# NP-100v12.net
KiCad netlist of a schematic drawn in EAGLE
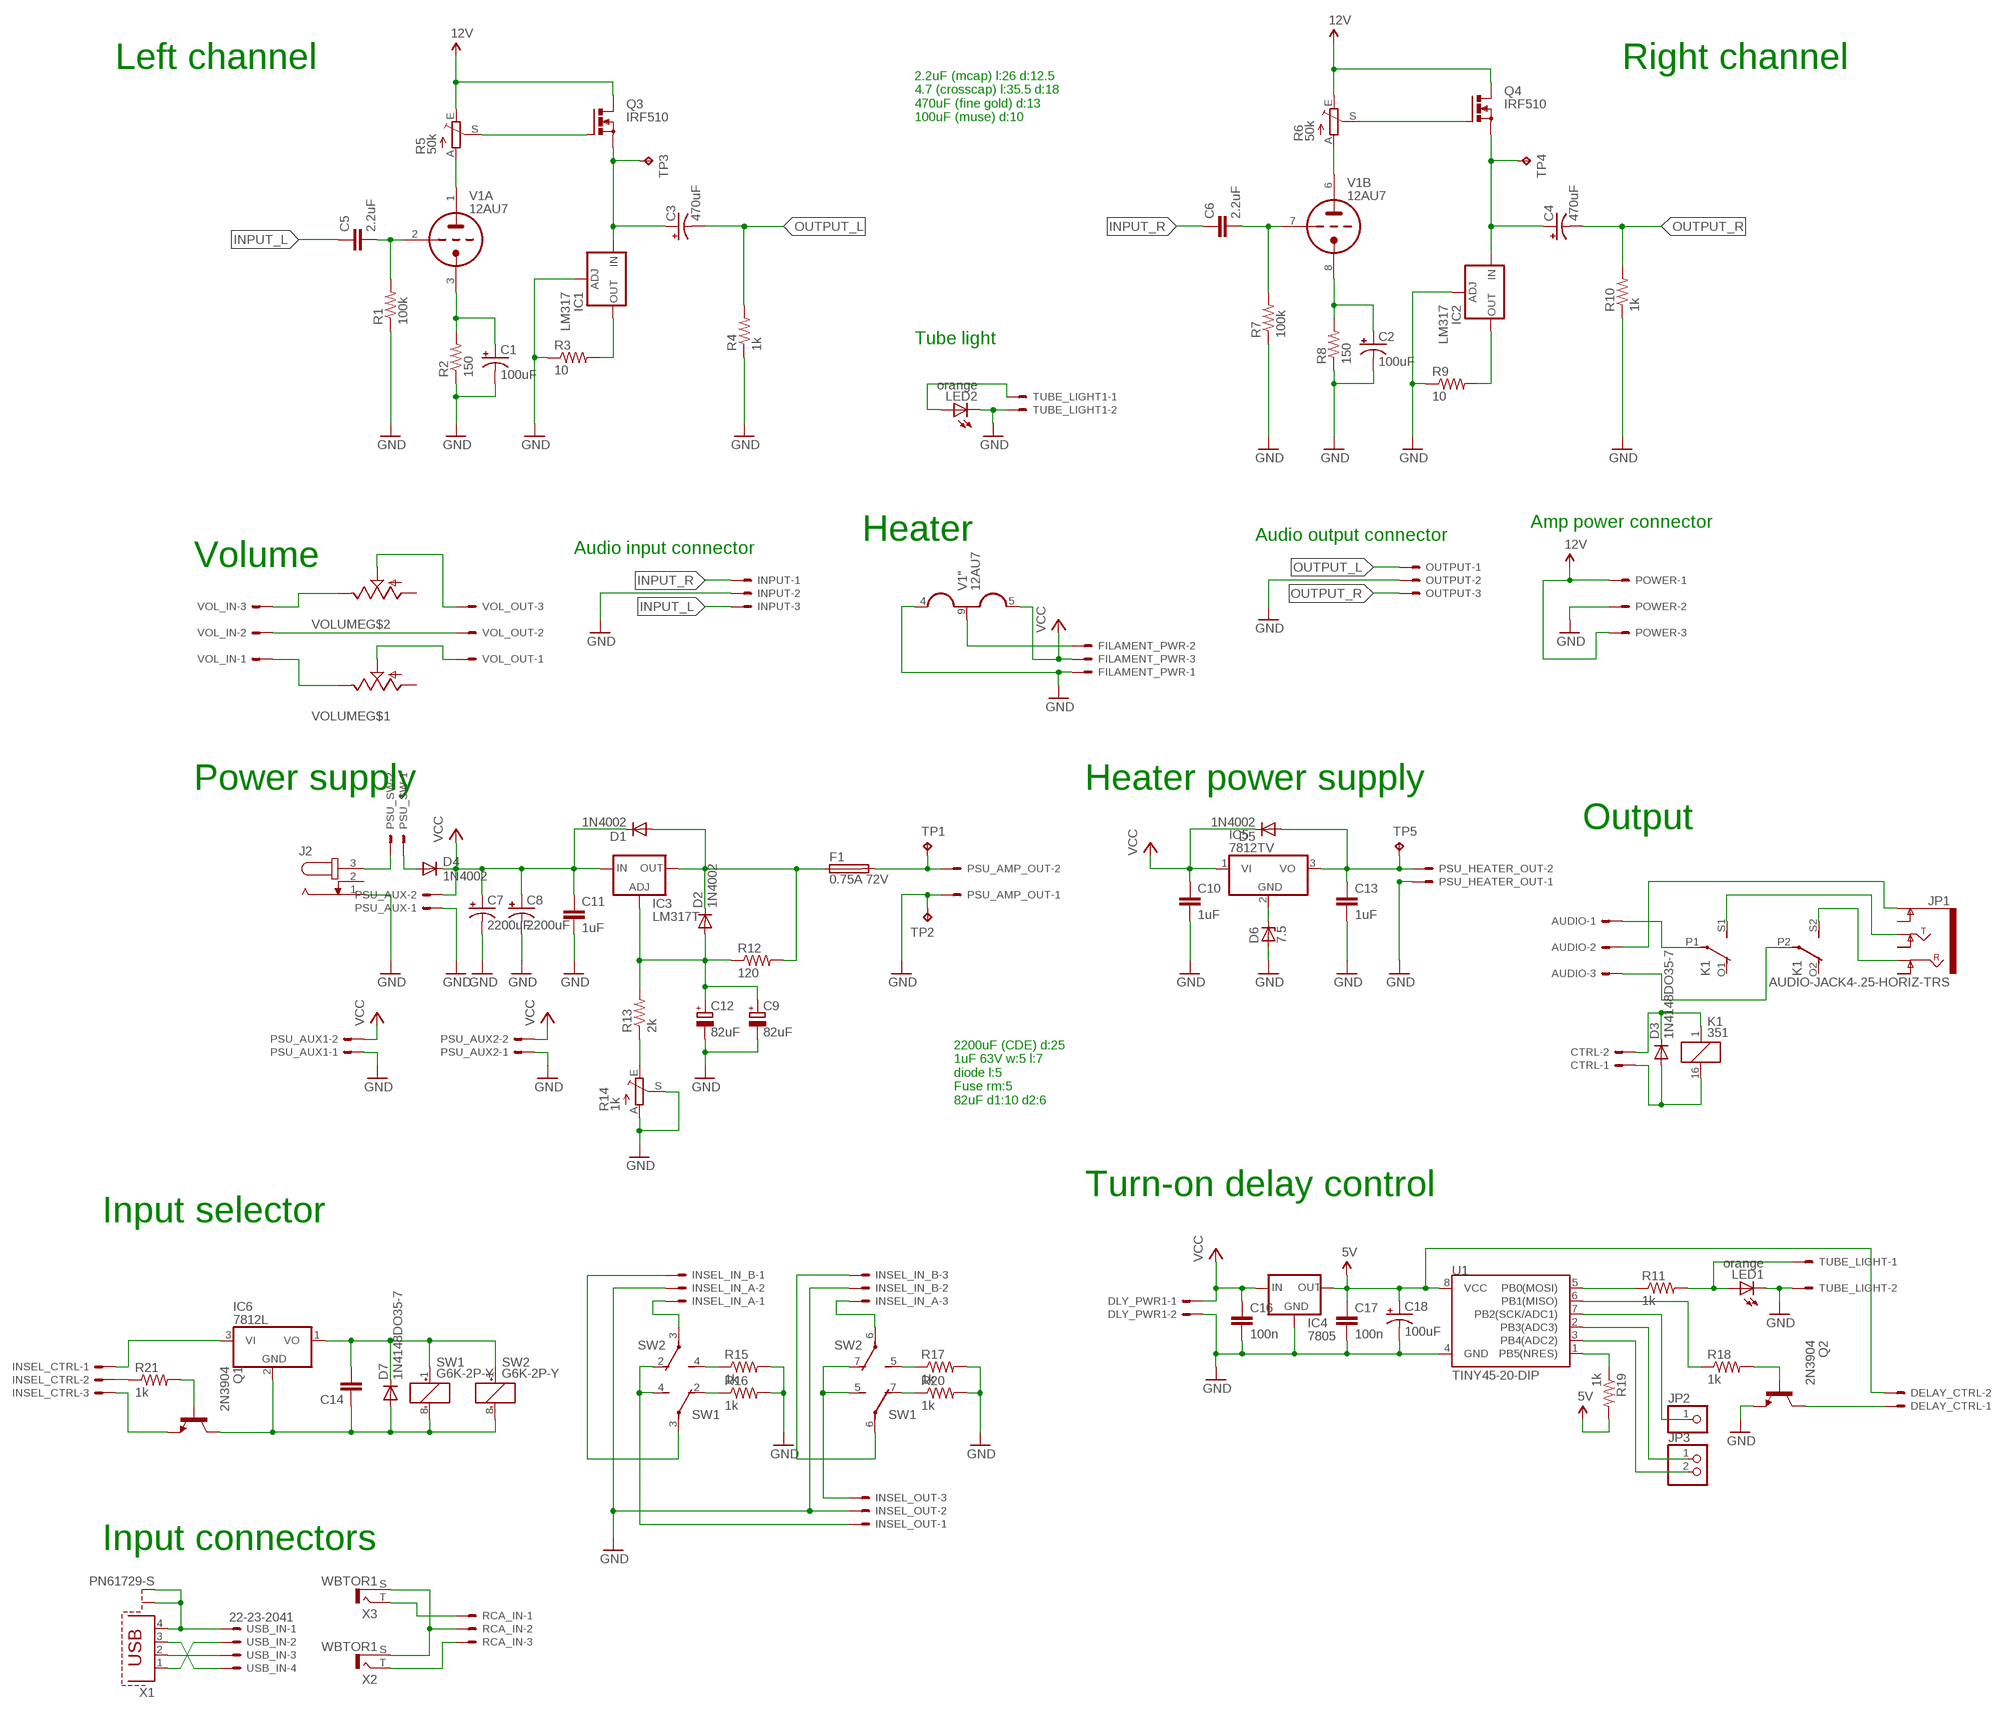
[diagram p0: schematic, sheet 1]

(export (version "E")
  (design (tool "Eeschema 10.0.6"))
  (components
    (comp (ref "AUDIO")
      (value "22-23-2031")
      (footprint "eagle-import:22-23-2031")
      (fields (field (name "MF") "MOLEX"))
      (libsource (lib "eagle-import") (part "22-23-2031"))
    )
    (comp (ref "C1")
      (value "100uF")
      (footprint "eagle-import:E5-10,5")
      (libsource (lib "eagle-import") (part "CPOL-USE5-10.5"))
    )
    (comp (ref "C2")
      (value "100uF")
      (footprint "eagle-import:E5-10,5")
      (libsource (lib "eagle-import") (part "CPOL-USE5-10.5"))
    )
    (comp (ref "C3")
      (value "470uF")
      (footprint "eagle-import:E5-13")
      (libsource (lib "eagle-import") (part "CPOL-USE5-13"))
    )
    (comp (ref "C4")
      (value "470uF")
      (footprint "eagle-import:E5-13")
      (libsource (lib "eagle-import") (part "CPOL-USE5-13"))
    )
    (comp (ref "C5")
      (value "2.2uF")
      (footprint "eagle-import:C37.5B19")
      (libsource (lib "eagle-import") (part "C37/19"))
    )
    (comp (ref "C6")
      (value "2.2uF")
      (footprint "eagle-import:C37.5B19")
      (libsource (lib "eagle-import") (part "C37/19"))
    )
    (comp (ref "C7")
      (value "2200uF")
      (footprint "eagle-import:EB25D")
      (libsource (lib "eagle-import") (part "CPOL-USE10-25"))
    )
    (comp (ref "C8")
      (value "2200uF")
      (footprint "eagle-import:EB25D")
      (libsource (lib "eagle-import") (part "CPOL-USE10-25"))
    )
    (comp (ref "C9")
      (value "82uF")
      (footprint "eagle-import:E2,5-6")
      (libsource (lib "eagle-import") (part "CPOL-EUE2.5-6"))
    )
    (comp (ref "C10")
      (value "1uF")
      (footprint "eagle-import:C5B4.5")
      (libsource (lib "eagle-import") (part "C5/4.5"))
    )
    (comp (ref "C11")
      (value "1uF")
      (footprint "eagle-import:C5B4.5")
      (libsource (lib "eagle-import") (part "C5/4.5"))
    )
    (comp (ref "C12")
      (value "82uF")
      (footprint "eagle-import:E5-10,5")
      (libsource (lib "eagle-import") (part "CPOL-EUE5-10.5"))
    )
    (comp (ref "C13")
      (value "1uF")
      (footprint "eagle-import:C5B4.5")
      (libsource (lib "eagle-import") (part "C5/4.5"))
    )
    (comp (ref "C14")
      (value "C5/2.5")
      (footprint "eagle-import:C5B2.5")
      (libsource (lib "eagle-import") (part "C5/2.5"))
    )
    (comp (ref "C16")
      (value "100n")
      (footprint "eagle-import:CAP-PTH-5MM")
      (libsource (lib "eagle-import") (part "CAPPTH1"))
    )
    (comp (ref "C17")
      (value "100n")
      (footprint "eagle-import:CAP-PTH-5MM")
      (libsource (lib "eagle-import") (part "CAPPTH1"))
    )
    (comp (ref "C18")
      (value "100uF")
      (footprint "eagle-import:E2,5-7")
      (libsource (lib "eagle-import") (part "CPOL-USE2.5-7"))
    )
    (comp (ref "CTRL")
      (value "22-23-2021")
      (footprint "eagle-import:22-23-2021")
      (fields (field (name "MF") "MOLEX"))
      (libsource (lib "eagle-import") (part "22-23-2021"))
    )
    (comp (ref "D1")
      (value "1N4002")
      (footprint "eagle-import:D-7.5")
      (libsource (lib "eagle-import") (part "DIODE-D-7.5"))
    )
    (comp (ref "D2")
      (value "1N4002")
      (footprint "eagle-import:D-7.5")
      (libsource (lib "eagle-import") (part "DIODE-D-7.5"))
    )
    (comp (ref "D3")
      (value "1N4148DO35-7")
      (footprint "eagle-import:DO35-7")
      (libsource (lib "eagle-import") (part "1N4148DO35-7"))
    )
    (comp (ref "D4")
      (value "1N4002")
      (footprint "eagle-import:D-5")
      (libsource (lib "eagle-import") (part "DIODE-D-5"))
    )
    (comp (ref "D5")
      (value "1N4002")
      (footprint "eagle-import:D-7.5")
      (libsource (lib "eagle-import") (part "DIODE-D-7.5"))
    )
    (comp (ref "D6")
      (value "7.5")
      (footprint "eagle-import:DO34Z7")
      (libsource (lib "eagle-import") (part "ZENER-DIODEDO34-7"))
    )
    (comp (ref "D7")
      (value "1N4148DO35-7")
      (footprint "eagle-import:DO35-7")
      (libsource (lib "eagle-import") (part "1N4148DO35-7"))
    )
    (comp (ref "DELAY_CTRL")
      (value "22-23-2021")
      (footprint "eagle-import:22-23-2021")
      (fields (field (name "MF") "MOLEX"))
      (libsource (lib "eagle-import") (part "22-23-2021"))
    )
    (comp (ref "DLY_PWR1")
      (value "22-23-2021")
      (footprint "eagle-import:22-23-2021")
      (fields (field (name "MF") "MOLEX"))
      (libsource (lib "eagle-import") (part "22-23-2021"))
    )
    (comp (ref "F1")
      (value "0.75A 72V")
      (footprint "eagle-import:TE5")
      (libsource (lib "eagle-import") (part "TE5"))
    )
    (comp (ref "FILAMENT_PWR")
      (value "22-23-2031")
      (footprint "eagle-import:22-23-2031")
      (fields (field (name "MF") "MOLEX"))
      (libsource (lib "eagle-import") (part "22-23-2031"))
    )
    (comp (ref "IC1")
      (value "LM317")
      (footprint "eagle-import:317TS")
      (libsource (lib "eagle-import") (part "LM317TS"))
    )
    (comp (ref "IC2")
      (value "LM317")
      (footprint "eagle-import:317TS")
      (libsource (lib "eagle-import") (part "LM317TS"))
    )
    (comp (ref "IC3")
      (value "LM317T")
      (footprint "eagle-import:317TS")
      (libsource (lib "eagle-import") (part "LM317TS"))
    )
    (comp (ref "IC4")
      (value "7805")
      (footprint "eagle-import:TO-92")
      (libsource (lib "eagle-import") (part "V_REG_78XXTO-92_UNTESTED"))
    )
    (comp (ref "IC5")
      (value "7812TV")
      (footprint "eagle-import:TO220V")
      (libsource (lib "eagle-import") (part "78TV12"))
    )
    (comp (ref "IC6")
      (value "7812L")
      (footprint "eagle-import:TO92")
      (libsource (lib "eagle-import") (part "78L12"))
    )
    (comp (ref "INPUT")
      (value "22-23-2031")
      (footprint "eagle-import:22-23-2031")
      (fields (field (name "MF") "MOLEX"))
      (libsource (lib "eagle-import") (part "22-23-2031"))
    )
    (comp (ref "INSEL_CTRL")
      (value "22-23-2031")
      (footprint "eagle-import:22-23-2031")
      (fields (field (name "MF") "MOLEX"))
      (libsource (lib "eagle-import") (part "22-23-2031"))
    )
    (comp (ref "INSEL_IN_A")
      (value "22-23-2031")
      (footprint "eagle-import:22-23-2031")
      (fields (field (name "MF") "MOLEX"))
      (libsource (lib "eagle-import") (part "22-23-2031"))
    )
    (comp (ref "INSEL_IN_B")
      (value "22-23-2031")
      (footprint "eagle-import:22-23-2031")
      (fields (field (name "MF") "MOLEX"))
      (libsource (lib "eagle-import") (part "22-23-2031"))
    )
    (comp (ref "INSEL_OUT")
      (value "22-23-2031")
      (footprint "eagle-import:22-23-2031")
      (fields (field (name "MF") "MOLEX"))
      (libsource (lib "eagle-import") (part "22-23-2031"))
    )
    (comp (ref "J2")
      (value "JACK-PLUG0")
      (footprint "eagle-import:SPC4077")
      (libsource (lib "eagle-import") (part "JACK-PLUG0"))
    )
    (comp (ref "JP1")
      (value "AUDIO-JACK4-.25-HORIZ-TRS")
      (footprint "eagle-import:AUDIO-JACK-.25-INCH-HORIZ-PTH")
      (libsource (lib "eagle-import") (part "AUDIO-JACK4-.25-HORIZ-TRS"))
    )
    (comp (ref "JP2")
      (value "PINHD-1X1")
      (footprint "eagle-import:1X01")
      (libsource (lib "eagle-import") (part "PINHD-1X1"))
    )
    (comp (ref "JP3")
      (value "PINHD-1X2")
      (footprint "eagle-import:1X02")
      (libsource (lib "eagle-import") (part "PINHD-1X2"))
    )
    (comp (ref "K1")
      (value "351")
      (footprint "eagle-import:351")
      (libsource (lib "eagle-import") (part "351"))
    )
    (comp (ref "LED1")
      (value "orange")
      (footprint "eagle-import:LED3MM")
      (libsource (lib "eagle-import") (part "LED3MM"))
    )
    (comp (ref "LED2")
      (value "orange")
      (footprint "eagle-import:LED3MM")
      (libsource (lib "eagle-import") (part "LED3MM"))
    )
    (comp (ref "OUTPUT")
      (value "22-23-2031")
      (footprint "eagle-import:22-23-2031")
      (fields (field (name "MF") "MOLEX"))
      (libsource (lib "eagle-import") (part "22-23-2031"))
    )
    (comp (ref "POWER")
      (value "22-23-2031")
      (footprint "eagle-import:22-23-2031")
      (fields (field (name "MF") "MOLEX"))
      (libsource (lib "eagle-import") (part "22-23-2031"))
    )
    (comp (ref "PSU_AMP_OUT")
      (value "22-23-2021")
      (footprint "eagle-import:22-23-2021")
      (fields (field (name "MF") "MOLEX"))
      (libsource (lib "eagle-import") (part "22-23-2021"))
    )
    (comp (ref "PSU_AUX")
      (value "22-23-2021")
      (footprint "eagle-import:22-23-2021")
      (fields (field (name "MF") "MOLEX"))
      (libsource (lib "eagle-import") (part "22-23-2021"))
    )
    (comp (ref "PSU_AUX1")
      (value "22-23-2021")
      (footprint "eagle-import:22-23-2021")
      (fields (field (name "MF") "MOLEX"))
      (libsource (lib "eagle-import") (part "22-23-2021"))
    )
    (comp (ref "PSU_AUX2")
      (value "22-23-2021")
      (footprint "eagle-import:22-23-2021")
      (fields (field (name "MF") "MOLEX"))
      (libsource (lib "eagle-import") (part "22-23-2021"))
    )
    (comp (ref "PSU_HEATER_OUT")
      (value "22-23-2021")
      (footprint "eagle-import:22-23-2021")
      (fields (field (name "MF") "MOLEX"))
      (libsource (lib "eagle-import") (part "22-23-2021"))
    )
    (comp (ref "PSU_SW")
      (value "22-23-2021")
      (footprint "eagle-import:22-23-2021")
      (fields (field (name "MF") "MOLEX"))
      (libsource (lib "eagle-import") (part "22-23-2021"))
    )
    (comp (ref "Q1")
      (value "2N3904")
      (footprint "eagle-import:TO92")
      (libsource (lib "eagle-import") (part "2N3904"))
    )
    (comp (ref "Q2")
      (value "2N3904")
      (footprint "eagle-import:TO92")
      (libsource (lib "eagle-import") (part "2N3904"))
    )
    (comp (ref "Q3")
      (value "IRF510")
      (footprint "eagle-import:TO220BV")
      (libsource (lib "eagle-import") (part "PMOSFET_NTO220BV"))
    )
    (comp (ref "Q4")
      (value "IRF510")
      (footprint "eagle-import:TO220BV")
      (libsource (lib "eagle-import") (part "PMOSFET_NTO220BV"))
    )
    (comp (ref "R1")
      (value "100k")
      (footprint "eagle-import:0207_10")
      (libsource (lib "eagle-import") (part "R-US_0207/10"))
    )
    (comp (ref "R2")
      (value "150")
      (footprint "eagle-import:0207_10")
      (libsource (lib "eagle-import") (part "R-US_0207/10"))
    )
    (comp (ref "R3")
      (value "10")
      (footprint "eagle-import:0207_10")
      (libsource (lib "eagle-import") (part "R-US_0207/10"))
    )
    (comp (ref "R4")
      (value "1k")
      (footprint "eagle-import:0207_10")
      (libsource (lib "eagle-import") (part "R-US_0207/10"))
    )
    (comp (ref "R5")
      (value "50k")
      (footprint "eagle-import:SP19L")
      (libsource (lib "eagle-import") (part "TRIM_EU-B90P"))
    )
    (comp (ref "R6")
      (value "50k")
      (footprint "eagle-import:SP19L")
      (libsource (lib "eagle-import") (part "TRIM_EU-B90P"))
    )
    (comp (ref "R7")
      (value "100k")
      (footprint "eagle-import:0207_10")
      (libsource (lib "eagle-import") (part "R-US_0207/10"))
    )
    (comp (ref "R8")
      (value "150")
      (footprint "eagle-import:0207_10")
      (libsource (lib "eagle-import") (part "R-US_0207/10"))
    )
    (comp (ref "R9")
      (value "10")
      (footprint "eagle-import:0207_10")
      (libsource (lib "eagle-import") (part "R-US_0207/10"))
    )
    (comp (ref "R10")
      (value "1k")
      (footprint "eagle-import:0207_10")
      (libsource (lib "eagle-import") (part "R-US_0207/10"))
    )
    (comp (ref "R11")
      (value "1k")
      (footprint "eagle-import:0204_7")
      (libsource (lib "eagle-import") (part "R-US_0204/7"))
    )
    (comp (ref "R12")
      (value "120")
      (footprint "eagle-import:AXIAL-0.3")
      (libsource (lib "eagle-import") (part "RESISTORAXIAL-0.3"))
    )
    (comp (ref "R13")
      (value "2k")
      (footprint "eagle-import:AXIAL-0.3")
      (libsource (lib "eagle-import") (part "RESISTORAXIAL-0.3"))
    )
    (comp (ref "R14")
      (value "1k")
      (footprint "eagle-import:S64Y")
      (libsource (lib "eagle-import") (part "TRIM_EU-S64Y"))
    )
    (comp (ref "R15")
      (value "1k")
      (footprint "eagle-import:AXIAL-0.3")
      (libsource (lib "eagle-import") (part "RESISTORAXIAL-0.3"))
    )
    (comp (ref "R16")
      (value "1k")
      (footprint "eagle-import:AXIAL-0.3")
      (libsource (lib "eagle-import") (part "RESISTORAXIAL-0.3"))
    )
    (comp (ref "R17")
      (value "1k")
      (footprint "eagle-import:AXIAL-0.3")
      (libsource (lib "eagle-import") (part "RESISTORAXIAL-0.3"))
    )
    (comp (ref "R18")
      (value "1k")
      (footprint "eagle-import:0204_7")
      (libsource (lib "eagle-import") (part "R-US_0204/7"))
    )
    (comp (ref "R19")
      (value "1k")
      (footprint "eagle-import:0204_7")
      (libsource (lib "eagle-import") (part "R-US_0204/7"))
    )
    (comp (ref "R20")
      (value "1k")
      (footprint "eagle-import:AXIAL-0.3")
      (libsource (lib "eagle-import") (part "RESISTORAXIAL-0.3"))
    )
    (comp (ref "R21")
      (value "1k")
      (footprint "eagle-import:0204_7")
      (libsource (lib "eagle-import") (part "R-US_0204/7"))
    )
    (comp (ref "RCA_IN")
      (value "22-23-2031")
      (footprint "eagle-import:22-23-2031")
      (fields (field (name "MF") "MOLEX"))
      (libsource (lib "eagle-import") (part "22-23-2031"))
    )
    (comp (ref "SW1")
      (value "G6K-2P-Y")
      (footprint "eagle-import:G6K-2P-Y")
      (fields (field (name "MF") "OMRON COMPONENTS USA") (field (name "MPN") "G6K-2P-Y DC12"))
      (libsource (lib "eagle-import") (part "G6K-2P-Y"))
    )
    (comp (ref "SW2")
      (value "G6K-2P-Y")
      (footprint "eagle-import:G6K-2P-Y")
      (fields (field (name "MF") "OMRON COMPONENTS USA") (field (name "MPN") "G6K-2P-Y DC12"))
      (libsource (lib "eagle-import") (part "G6K-2P-Y"))
    )
    (comp (ref "TP1")
      (value "TPPAD1-17")
      (footprint "eagle-import:P1-17")
      (libsource (lib "eagle-import") (part "TPPAD1-17"))
    )
    (comp (ref "TP2")
      (value "TPPAD1-17")
      (footprint "eagle-import:P1-17")
      (libsource (lib "eagle-import") (part "TPPAD1-17"))
    )
    (comp (ref "TP3")
      (value "TPPAD1-17")
      (footprint "eagle-import:P1-17")
      (libsource (lib "eagle-import") (part "TPPAD1-17"))
    )
    (comp (ref "TP4")
      (value "TPPAD1-17")
      (footprint "eagle-import:P1-17")
      (libsource (lib "eagle-import") (part "TPPAD1-17"))
    )
    (comp (ref "TP5")
      (value "TPPAD1-17")
      (footprint "eagle-import:P1-17")
      (libsource (lib "eagle-import") (part "TPPAD1-17"))
    )
    (comp (ref "TUBE_LIGHT")
      (value "22-23-2021")
      (footprint "eagle-import:22-23-2021")
      (fields (field (name "MF") "MOLEX"))
      (libsource (lib "eagle-import") (part "22-23-2021"))
    )
    (comp (ref "TUBE_LIGHT1")
      (value "22-23-2021")
      (footprint "eagle-import:22-23-2021")
      (fields (field (name "MF") "MOLEX"))
      (libsource (lib "eagle-import") (part "22-23-2021"))
    )
    (comp (ref "U1")
      (value "TINY45-20-DIP")
      (footprint "eagle-import:DIP08")
      (libsource (lib "eagle-import") (part "ATTINY45TINY45-20-DIP"))
    )
    (comp (ref "USB_IN")
      (value "22-23-2041")
      (footprint "eagle-import:22-23-2041")
      (fields (field (name "MF") "MOLEX"))
      (libsource (lib "eagle-import") (part "22-23-2041"))
    )
    (comp (ref "V1")
      (value "12AU7")
      (footprint "eagle-import:NOVAL")
      (libsource (lib "eagle-import") (part "12AU7-P"))
    )
    (comp (ref "VOLUME")
      (value "ALPS_BLUE")
      (footprint "eagle-import:ALPS_RK27")
      (libsource (lib "eagle-import") (part "ALPS_BLUE"))
    )
    (comp (ref "VOL_IN")
      (value "22-23-2031")
      (footprint "eagle-import:22-23-2031")
      (fields (field (name "MF") "MOLEX"))
      (libsource (lib "eagle-import") (part "22-23-2031"))
    )
    (comp (ref "VOL_OUT")
      (value "22-23-2031")
      (footprint "eagle-import:22-23-2031")
      (fields (field (name "MF") "MOLEX"))
      (libsource (lib "eagle-import") (part "22-23-2031"))
    )
    (comp (ref "X1")
      (value "PN61729-S")
      (footprint "eagle-import:PN61729-S")
      (libsource (lib "eagle-import") (part "PN61729-S"))
    )
    (comp (ref "X2")
      (value "WBTOR1")
      (footprint "eagle-import:WBTOR1")
      (fields (field (name "MPN") "WBTOR 1 BLACK"))
      (libsource (lib "eagle-import") (part "WBTOR1"))
    )
    (comp (ref "X3")
      (value "WBTOR1")
      (footprint "eagle-import:WBTOR1")
      (fields (field (name "MPN") "WBTOR 1 BLACK"))
      (libsource (lib "eagle-import") (part "WBTOR1"))
    )
  )
  (nets
    (net (code "1") (name "5V") (class "Default")
      (node (ref "C17") (pin "1") (pinfunction "1_1") (pintype "passive"))
      (node (ref "C18") (pin "+") (pinfunction "+_+") (pintype "passive"))
      (node (ref "DELAY_CTRL") (pin "2") (pinfunction "S_2") (pintype "passive"))
      (node (ref "IC4") (pin "3") (pinfunction "OUT_3") (pintype "output"))
      (node (ref "R19") (pin "2") (pinfunction "2_2") (pintype "passive"))
      (node (ref "U1") (pin "8") (pinfunction "VCC_8") (pintype "bidirectional"))
    )
    (net (code "2") (name "12V") (class "Default")
      (node (ref "POWER") (pin "1") (pinfunction "S_1") (pintype "passive"))
      (node (ref "POWER") (pin "3") (pinfunction "S_3") (pintype "passive"))
      (node (ref "Q3") (pin "D") (pinfunction "D_D") (pintype "passive"))
      (node (ref "Q4") (pin "D") (pinfunction "D_D") (pintype "passive"))
      (node (ref "R5") (pin "E") (pinfunction "E_E") (pintype "passive"))
      (node (ref "R6") (pin "E") (pinfunction "E_E") (pintype "passive"))
    )
    (net (code "3") (name "GND") (class "Default")
      (node (ref "C1") (pin "-") (pinfunction "-_-") (pintype "passive"))
      (node (ref "C10") (pin "2") (pinfunction "2_2") (pintype "passive"))
      (node (ref "C11") (pin "2") (pinfunction "2_2") (pintype "passive"))
      (node (ref "C12") (pin "-") (pinfunction "-_-") (pintype "passive"))
      (node (ref "C13") (pin "2") (pinfunction "2_2") (pintype "passive"))
      (node (ref "C16") (pin "2") (pinfunction "2_2") (pintype "passive"))
      (node (ref "C17") (pin "2") (pinfunction "2_2") (pintype "passive"))
      (node (ref "C18") (pin "-") (pinfunction "-_-") (pintype "passive"))
      (node (ref "C2") (pin "-") (pinfunction "-_-") (pintype "passive"))
      (node (ref "C7") (pin "-") (pinfunction "-_-") (pintype "passive"))
      (node (ref "C8") (pin "-") (pinfunction "-_-") (pintype "passive"))
      (node (ref "C9") (pin "-") (pinfunction "-_-") (pintype "passive"))
      (node (ref "D6") (pin "A") (pinfunction "A_A") (pintype "passive"))
      (node (ref "DLY_PWR1") (pin "2") (pinfunction "S_2") (pintype "passive"))
      (node (ref "FILAMENT_PWR") (pin "1") (pinfunction "S_1") (pintype "passive"))
      (node (ref "IC1") (pin "1") (pinfunction "ADJ_1") (pintype "input"))
      (node (ref "IC2") (pin "1") (pinfunction "ADJ_1") (pintype "input"))
      (node (ref "IC4") (pin "1") (pinfunction "GND_1") (pintype "input"))
      (node (ref "INPUT") (pin "2") (pinfunction "S_2") (pintype "passive"))
      (node (ref "INSEL_IN_A") (pin "2") (pinfunction "S_2") (pintype "passive"))
      (node (ref "INSEL_IN_B") (pin "2") (pinfunction "S_2") (pintype "passive"))
      (node (ref "INSEL_OUT") (pin "2") (pinfunction "S_2") (pintype "passive"))
      (node (ref "J2") (pin "1") (pinfunction "1_1") (pintype "passive"))
      (node (ref "LED1") (pin "K") (pinfunction "C_K") (pintype "passive"))
      (node (ref "LED2") (pin "K") (pinfunction "C_K") (pintype "passive"))
      (node (ref "OUTPUT") (pin "2") (pinfunction "S_2") (pintype "passive"))
      (node (ref "POWER") (pin "2") (pinfunction "S_2") (pintype "passive"))
      (node (ref "PSU_AMP_OUT") (pin "1") (pinfunction "S_1") (pintype "passive"))
      (node (ref "PSU_AUX") (pin "1") (pinfunction "S_1") (pintype "passive"))
      (node (ref "PSU_AUX1") (pin "1") (pinfunction "S_1") (pintype "passive"))
      (node (ref "PSU_AUX2") (pin "1") (pinfunction "S_1") (pintype "passive"))
      (node (ref "PSU_HEATER_OUT") (pin "1") (pinfunction "S_1") (pintype "passive"))
      (node (ref "Q2") (pin "3") (pinfunction "E_3") (pintype "passive"))
      (node (ref "R1") (pin "1") (pinfunction "1_1") (pintype "passive"))
      (node (ref "R10") (pin "1") (pinfunction "1_1") (pintype "passive"))
      (node (ref "R14") (pin "A") (pinfunction "A_A") (pintype "passive"))
      (node (ref "R14") (pin "S") (pinfunction "S_S") (pintype "passive"))
      (node (ref "R15") (pin "P$2") (pinfunction "2_P$2") (pintype "passive"))
      (node (ref "R16") (pin "P$2") (pinfunction "2_P$2") (pintype "passive"))
      (node (ref "R17") (pin "P$2") (pinfunction "2_P$2") (pintype "passive"))
      (node (ref "R2") (pin "1") (pinfunction "1_1") (pintype "passive"))
      (node (ref "R20") (pin "P$2") (pinfunction "2_P$2") (pintype "passive"))
      (node (ref "R3") (pin "1") (pinfunction "1_1") (pintype "passive"))
      (node (ref "R4") (pin "1") (pinfunction "1_1") (pintype "passive"))
      (node (ref "R7") (pin "1") (pinfunction "1_1") (pintype "passive"))
      (node (ref "R8") (pin "1") (pinfunction "1_1") (pintype "passive"))
      (node (ref "R9") (pin "1") (pinfunction "1_1") (pintype "passive"))
      (node (ref "TP2") (pin "TP") (pinfunction "TP_TP") (pintype "input"))
      (node (ref "TUBE_LIGHT") (pin "2") (pinfunction "S_2") (pintype "passive"))
      (node (ref "TUBE_LIGHT1") (pin "2") (pinfunction "S_2") (pintype "passive"))
      (node (ref "U1") (pin "4") (pinfunction "GND_4") (pintype "bidirectional"))
      (node (ref "V1") (pin "4") (pinfunction "H1_4") (pintype "passive"))
    )
    (net (code "4") (name "INPUT_L") (class "Default")
      (node (ref "C5") (pin "1") (pinfunction "1_1") (pintype "passive"))
      (node (ref "INPUT") (pin "3") (pinfunction "S_3") (pintype "passive"))
    )
    (net (code "5") (name "INPUT_R") (class "Default")
      (node (ref "C6") (pin "1") (pinfunction "1_1") (pintype "passive"))
      (node (ref "INPUT") (pin "1") (pinfunction "S_1") (pintype "passive"))
    )
    (net (code "6") (name "Net-(AUDIOA-S)") (class "Default")
      (node (ref "AUDIO") (pin "1") (pinfunction "S_1") (pintype "passive"))
      (node (ref "K1") (pin "P1") (pinfunction "P_P1") (pintype "passive"))
    )
    (net (code "7") (name "Net-(AUDIOB-S)") (class "Default")
      (node (ref "AUDIO") (pin "2") (pinfunction "S_2") (pintype "passive"))
      (node (ref "JP1") (pin "SLEEVE") (pinfunction "EARTH_SLEEVE") (pintype "bidirectional"))
    )
    (net (code "8") (name "Net-(AUDIOC-S)") (class "Default")
      (node (ref "AUDIO") (pin "3") (pinfunction "S_3") (pintype "passive"))
      (node (ref "K1") (pin "P2") (pinfunction "P_P2") (pintype "passive"))
    )
    (net (code "9") (name "Net-(CTRLA-S)") (class "Default")
      (node (ref "CTRL") (pin "1") (pinfunction "S_1") (pintype "passive"))
      (node (ref "D3") (pin "A") (pinfunction "A_A") (pintype "passive"))
      (node (ref "K1") (pin "16") (pinfunction "2_16") (pintype "passive"))
    )
    (net (code "10") (name "Net-(CTRLB-S)") (class "Default")
      (node (ref "CTRL") (pin "2") (pinfunction "S_2") (pintype "passive"))
      (node (ref "D3") (pin "C") (pinfunction "C_C") (pintype "passive"))
      (node (ref "K1") (pin "1") (pinfunction "1_1") (pintype "passive"))
    )
    (net (code "11") (name "Net-(DELAY_CTRLA-S)") (class "Default")
      (node (ref "DELAY_CTRL") (pin "1") (pinfunction "S_1") (pintype "passive"))
      (node (ref "Q2") (pin "1") (pinfunction "C_1") (pintype "passive"))
    )
    (net (code "12") (name "Net-(FILAMENT_PWRB-S)") (class "Default")
      (node (ref "FILAMENT_PWR") (pin "2") (pinfunction "S_2") (pintype "passive"))
      (node (ref "V1") (pin "9") (pinfunction "H2_9") (pintype "passive"))
    )
    (net (code "13") (name "Net-(IC1-IN)") (class "Default")
      (node (ref "C3") (pin "+") (pinfunction "+_+") (pintype "passive"))
      (node (ref "IC1") (pin "3") (pinfunction "IN_3") (pintype "input"))
      (node (ref "Q3") (pin "S") (pinfunction "S_S") (pintype "passive"))
      (node (ref "TP3") (pin "TP") (pinfunction "TP_TP") (pintype "input"))
    )
    (net (code "14") (name "Net-(IC1-OUT)") (class "Default")
      (node (ref "IC1") (pin "2") (pinfunction "OUT_2") (pintype "passive"))
      (node (ref "R3") (pin "2") (pinfunction "2_2") (pintype "passive"))
    )
    (net (code "15") (name "Net-(IC2-IN)") (class "Default")
      (node (ref "C4") (pin "+") (pinfunction "+_+") (pintype "passive"))
      (node (ref "IC2") (pin "3") (pinfunction "IN_3") (pintype "input"))
      (node (ref "Q4") (pin "S") (pinfunction "S_S") (pintype "passive"))
      (node (ref "TP4") (pin "TP") (pinfunction "TP_TP") (pintype "input"))
    )
    (net (code "16") (name "Net-(IC2-OUT)") (class "Default")
      (node (ref "IC2") (pin "2") (pinfunction "OUT_2") (pintype "passive"))
      (node (ref "R9") (pin "2") (pinfunction "2_2") (pintype "passive"))
    )
    (net (code "17") (name "Net-(IC3-ADJ)") (class "Default")
      (node (ref "C12") (pin "+") (pinfunction "+_+") (pintype "passive"))
      (node (ref "C9") (pin "+") (pinfunction "+_+") (pintype "passive"))
      (node (ref "D2") (pin "A") (pinfunction "A_A") (pintype "passive"))
      (node (ref "IC3") (pin "1") (pinfunction "ADJ_1") (pintype "input"))
      (node (ref "R12") (pin "P$1") (pinfunction "1_P$1") (pintype "passive"))
      (node (ref "R13") (pin "P$2") (pinfunction "2_P$2") (pintype "passive"))
    )
    (net (code "18") (name "Net-(IC3-OUT)") (class "Default")
      (node (ref "D1") (pin "A") (pinfunction "A_A") (pintype "passive"))
      (node (ref "D2") (pin "C") (pinfunction "C_C") (pintype "passive"))
      (node (ref "F1") (pin "1") (pinfunction "1_1") (pintype "passive"))
      (node (ref "IC3") (pin "2") (pinfunction "OUT_2") (pintype "passive"))
      (node (ref "R12") (pin "P$2") (pinfunction "2_P$2") (pintype "passive"))
    )
    (net (code "19") (name "Net-(IC5-GND)") (class "Default")
      (node (ref "D6") (pin "C") (pinfunction "C_C") (pintype "passive"))
      (node (ref "IC5") (pin "2") (pinfunction "GND_2") (pintype "passive"))
    )
    (net (code "20") (name "Net-(IC5-VO)") (class "Default")
      (node (ref "C13") (pin "1") (pinfunction "1_1") (pintype "passive"))
      (node (ref "D5") (pin "A") (pinfunction "A_A") (pintype "passive"))
      (node (ref "IC5") (pin "3") (pinfunction "VO_3") (pintype "passive"))
      (node (ref "PSU_HEATER_OUT") (pin "2") (pinfunction "S_2") (pintype "passive"))
      (node (ref "TP5") (pin "TP") (pinfunction "TP_TP") (pintype "input"))
    )
    (net (code "21") (name "Net-(IC6-GND)") (class "Default")
      (node (ref "C14") (pin "1") (pinfunction "1_1") (pintype "passive"))
      (node (ref "D7") (pin "A") (pinfunction "A_A") (pintype "passive"))
      (node (ref "IC6") (pin "2") (pinfunction "GND_2") (pintype "passive"))
      (node (ref "Q1") (pin "1") (pinfunction "C_1") (pintype "passive"))
      (node (ref "SW1") (pin "8") (pinfunction "-_8") (pintype "passive"))
      (node (ref "SW2") (pin "8") (pinfunction "-_8") (pintype "passive"))
    )
    (net (code "22") (name "Net-(IC6-VI)") (class "Default")
      (node (ref "IC6") (pin "3") (pinfunction "VI_3") (pintype "input"))
      (node (ref "INSEL_CTRL") (pin "1") (pinfunction "S_1") (pintype "passive"))
    )
    (net (code "23") (name "Net-(IC6-VO)") (class "Default")
      (node (ref "C14") (pin "2") (pinfunction "2_2") (pintype "passive"))
      (node (ref "D7") (pin "C") (pinfunction "C_C") (pintype "passive"))
      (node (ref "IC6") (pin "1") (pinfunction "VO_1") (pintype "passive"))
      (node (ref "SW1") (pin "1") (pinfunction "+_1") (pintype "passive"))
      (node (ref "SW2") (pin "1") (pinfunction "+_1") (pintype "passive"))
    )
    (net (code "24") (name "Net-(INSEL_CTRLB-S)") (class "Default")
      (node (ref "INSEL_CTRL") (pin "2") (pinfunction "S_2") (pintype "passive"))
      (node (ref "R21") (pin "1") (pinfunction "1_1") (pintype "passive"))
    )
    (net (code "25") (name "Net-(INSEL_CTRLC-S)") (class "Default")
      (node (ref "INSEL_CTRL") (pin "3") (pinfunction "S_3") (pintype "passive"))
      (node (ref "Q1") (pin "3") (pinfunction "E_3") (pintype "passive"))
    )
    (net (code "26") (name "Net-(INSEL_IN_AA-S)") (class "Default")
      (node (ref "INSEL_IN_A") (pin "1") (pinfunction "S_1") (pintype "passive"))
      (node (ref "SW2") (pin "3") (pinfunction "P_3") (pintype "passive"))
    )
    (net (code "27") (name "Net-(INSEL_IN_AC-S)") (class "Default")
      (node (ref "INSEL_IN_A") (pin "3") (pinfunction "S_3") (pintype "passive"))
      (node (ref "SW2") (pin "6") (pinfunction "P_6") (pintype "passive"))
    )
    (net (code "28") (name "Net-(INSEL_IN_BA-S)") (class "Default")
      (node (ref "INSEL_IN_B") (pin "1") (pinfunction "S_1") (pintype "passive"))
      (node (ref "SW1") (pin "3") (pinfunction "P_3") (pintype "passive"))
    )
    (net (code "29") (name "Net-(INSEL_IN_BC-S)") (class "Default")
      (node (ref "INSEL_IN_B") (pin "3") (pinfunction "S_3") (pintype "passive"))
      (node (ref "SW1") (pin "6") (pinfunction "P_6") (pintype "passive"))
    )
    (net (code "30") (name "Net-(INSEL_OUTA-S)") (class "Default")
      (node (ref "INSEL_OUT") (pin "1") (pinfunction "S_1") (pintype "passive"))
      (node (ref "SW1") (pin "4") (pinfunction "S_4") (pintype "passive"))
      (node (ref "SW2") (pin "2") (pinfunction "O_2") (pintype "passive"))
    )
    (net (code "31") (name "Net-(INSEL_OUTC-S)") (class "Default")
      (node (ref "INSEL_OUT") (pin "3") (pinfunction "S_3") (pintype "passive"))
      (node (ref "SW1") (pin "5") (pinfunction "S_5") (pintype "passive"))
      (node (ref "SW2") (pin "7") (pinfunction "O_7") (pintype "passive"))
    )
    (net (code "32") (name "Net-(K1B-S)") (class "Default")
      (node (ref "JP1") (pin "TIP") (pinfunction "TIP_TIP") (pintype "bidirectional"))
      (node (ref "K1") (pin "S1") (pinfunction "S_S1") (pintype "passive"))
    )
    (net (code "33") (name "Net-(K1C-S)") (class "Default")
      (node (ref "JP1") (pin "RING") (pinfunction "RING_RING") (pintype "bidirectional"))
      (node (ref "K1") (pin "S2") (pinfunction "S_S2") (pintype "passive"))
    )
    (net (code "34") (name "Net-(PSU_AMP_OUTB-S)") (class "Default")
      (node (ref "F1") (pin "2") (pinfunction "2_2") (pintype "passive"))
      (node (ref "PSU_AMP_OUT") (pin "2") (pinfunction "S_2") (pintype "passive"))
      (node (ref "TP1") (pin "TP") (pinfunction "TP_TP") (pintype "input"))
    )
    (net (code "35") (name "Net-(PSU_SWA-S)") (class "Default")
      (node (ref "D4") (pin "A") (pinfunction "A_A") (pintype "passive"))
      (node (ref "PSU_SW") (pin "1") (pinfunction "S_1") (pintype "passive"))
    )
    (net (code "36") (name "Net-(PSU_SWB-S)") (class "Default")
      (node (ref "J2") (pin "3") (pinfunction "3_3") (pintype "passive"))
      (node (ref "PSU_SW") (pin "2") (pinfunction "S_2") (pintype "passive"))
    )
    (net (code "37") (name "Net-(Q1-B)") (class "Default")
      (node (ref "Q1") (pin "2") (pinfunction "B_2") (pintype "passive"))
      (node (ref "R21") (pin "2") (pinfunction "2_2") (pintype "passive"))
    )
    (net (code "38") (name "Net-(Q2-B)") (class "Default")
      (node (ref "Q2") (pin "2") (pinfunction "B_2") (pintype "passive"))
      (node (ref "R18") (pin "2") (pinfunction "2_2") (pintype "passive"))
    )
    (net (code "39") (name "Net-(Q3-PadG)") (class "Default")
      (node (ref "Q3") (pin "G") (pinfunction "G_G") (pintype "passive"))
      (node (ref "R5") (pin "S") (pinfunction "S_S") (pintype "passive"))
    )
    (net (code "40") (name "Net-(Q4-PadG)") (class "Default")
      (node (ref "Q4") (pin "G") (pinfunction "G_G") (pintype "passive"))
      (node (ref "R6") (pin "S") (pinfunction "S_S") (pintype "passive"))
    )
    (net (code "41") (name "Net-(R13-1)") (class "Default")
      (node (ref "R13") (pin "P$1") (pinfunction "1_P$1") (pintype "passive"))
      (node (ref "R14") (pin "E") (pinfunction "E_E") (pintype "passive"))
    )
    (net (code "42") (name "Net-(R15-1)") (class "Default")
      (node (ref "R15") (pin "P$1") (pinfunction "1_P$1") (pintype "passive"))
      (node (ref "SW2") (pin "4") (pinfunction "S_4") (pintype "passive"))
    )
    (net (code "43") (name "Net-(R16-1)") (class "Default")
      (node (ref "R16") (pin "P$1") (pinfunction "1_P$1") (pintype "passive"))
      (node (ref "SW1") (pin "2") (pinfunction "O_2") (pintype "passive"))
    )
    (net (code "44") (name "Net-(R17-1)") (class "Default")
      (node (ref "R17") (pin "P$1") (pinfunction "1_P$1") (pintype "passive"))
      (node (ref "SW2") (pin "5") (pinfunction "S_5") (pintype "passive"))
    )
    (net (code "45") (name "Net-(R20-1)") (class "Default")
      (node (ref "R20") (pin "P$1") (pinfunction "1_P$1") (pintype "passive"))
      (node (ref "SW1") (pin "7") (pinfunction "O_7") (pintype "passive"))
    )
    (net (code "46") (name "Net-(RCA_INA-S)") (class "Default")
      (node (ref "RCA_IN") (pin "1") (pinfunction "S_1") (pintype "passive"))
      (node (ref "X3") (pin "T") (pinfunction "T_T") (pintype "passive"))
    )
    (net (code "47") (name "Net-(RCA_INB-S)") (class "Default")
      (node (ref "RCA_IN") (pin "2") (pinfunction "S_2") (pintype "passive"))
      (node (ref "X2") (pin "S") (pinfunction "S_S") (pintype "passive"))
      (node (ref "X3") (pin "S") (pinfunction "S_S") (pintype "passive"))
    )
    (net (code "48") (name "Net-(RCA_INC-S)") (class "Default")
      (node (ref "RCA_IN") (pin "3") (pinfunction "S_3") (pintype "passive"))
      (node (ref "X2") (pin "T") (pinfunction "T_T") (pintype "passive"))
    )
    (net (code "49") (name "Net-(TUBE_LIGHT1A-S)") (class "Default")
      (node (ref "LED2") (pin "A") (pinfunction "A_A") (pintype "passive"))
      (node (ref "TUBE_LIGHT1") (pin "1") (pinfunction "S_1") (pintype "passive"))
    )
    (net (code "50") (name "Net-(TUBE_LIGHTA-S)") (class "Default")
      (node (ref "LED1") (pin "A") (pinfunction "A_A") (pintype "passive"))
      (node (ref "R11") (pin "2") (pinfunction "2_2") (pintype "passive"))
      (node (ref "TUBE_LIGHT") (pin "1") (pinfunction "S_1") (pintype "passive"))
    )
    (net (code "51") (name "Net-(U1-PB0(MOSI))") (class "Default")
      (node (ref "R11") (pin "1") (pinfunction "1_1") (pintype "passive"))
      (node (ref "U1") (pin "5") (pinfunction "PB0(MOSI)_5") (pintype "bidirectional"))
    )
    (net (code "52") (name "Net-(U1-PB1(MISO))") (class "Default")
      (node (ref "R18") (pin "1") (pinfunction "1_1") (pintype "passive"))
      (node (ref "U1") (pin "6") (pinfunction "PB1(MISO)_6") (pintype "bidirectional"))
    )
    (net (code "53") (name "Net-(U1-PB2(SCK{slash}ADC1))") (class "Default")
      (node (ref "JP2") (pin "1") (pinfunction "1_1") (pintype "passive"))
      (node (ref "U1") (pin "7") (pinfunction "PB2(SCK/ADC1)_7") (pintype "bidirectional"))
    )
    (net (code "54") (name "Net-(U1-PB3(ADC3))") (class "Default")
      (node (ref "JP3") (pin "1") (pinfunction "1_1") (pintype "passive"))
      (node (ref "U1") (pin "2") (pinfunction "PB3(ADC3)_2") (pintype "bidirectional"))
    )
    (net (code "55") (name "Net-(U1-PB4(ADC2))") (class "Default")
      (node (ref "JP3") (pin "2") (pinfunction "2_2") (pintype "passive"))
      (node (ref "U1") (pin "3") (pinfunction "PB4(ADC2)_3") (pintype "bidirectional"))
    )
    (net (code "56") (name "Net-(U1-PB5(NRES))") (class "Default")
      (node (ref "R19") (pin "1") (pinfunction "1_1") (pintype "passive"))
      (node (ref "U1") (pin "1") (pinfunction "PB5(NRES)_1") (pintype "bidirectional"))
    )
    (net (code "57") (name "Net-(USB_INA-S)") (class "Default")
      (node (ref "USB_IN") (pin "1") (pinfunction "S_1") (pintype "passive"))
      (node (ref "X1") (pin "4") (pinfunction "4_4") (pintype "passive"))
      (node (ref "X1") (pin "S1") (pinfunction "S1_S1") (pintype "passive"))
      (node (ref "X1") (pin "S2") (pinfunction "S2_S2") (pintype "passive"))
    )
    (net (code "58") (name "Net-(USB_INB-S)") (class "Default")
      (node (ref "USB_IN") (pin "2") (pinfunction "S_2") (pintype "passive"))
      (node (ref "X1") (pin "1") (pinfunction "1_1") (pintype "passive"))
    )
    (net (code "59") (name "Net-(USB_INC-S)") (class "Default")
      (node (ref "USB_IN") (pin "3") (pinfunction "S_3") (pintype "passive"))
      (node (ref "X1") (pin "2") (pinfunction "2_2") (pintype "passive"))
    )
    (net (code "60") (name "Net-(USB_IND-S)") (class "Default")
      (node (ref "USB_IN") (pin "4") (pinfunction "S_4") (pintype "passive"))
      (node (ref "X1") (pin "3") (pinfunction "3_3") (pintype "passive"))
    )
    (net (code "61") (name "Net-(V1B-TA)") (class "Default")
      (node (ref "R5") (pin "A") (pinfunction "A_A") (pintype "passive"))
      (node (ref "V1") (pin "1") (pinfunction "TA_1") (pintype "passive"))
    )
    (net (code "62") (name "Net-(V1B-TG)") (class "Default")
      (node (ref "C5") (pin "2") (pinfunction "2_2") (pintype "passive"))
      (node (ref "R1") (pin "2") (pinfunction "2_2") (pintype "passive"))
      (node (ref "V1") (pin "2") (pinfunction "TG_2") (pintype "passive"))
    )
    (net (code "63") (name "Net-(V1B-TK)") (class "Default")
      (node (ref "C1") (pin "+") (pinfunction "+_+") (pintype "passive"))
      (node (ref "R2") (pin "2") (pinfunction "2_2") (pintype "passive"))
      (node (ref "V1") (pin "3") (pinfunction "TK_3") (pintype "passive"))
    )
    (net (code "64") (name "Net-(V1C-TA)") (class "Default")
      (node (ref "R6") (pin "A") (pinfunction "A_A") (pintype "passive"))
      (node (ref "V1") (pin "6") (pinfunction "TA_6") (pintype "passive"))
    )
    (net (code "65") (name "Net-(V1C-TG)") (class "Default")
      (node (ref "C6") (pin "2") (pinfunction "2_2") (pintype "passive"))
      (node (ref "R7") (pin "2") (pinfunction "2_2") (pintype "passive"))
      (node (ref "V1") (pin "7") (pinfunction "TG_7") (pintype "passive"))
    )
    (net (code "66") (name "Net-(V1C-TK)") (class "Default")
      (node (ref "C2") (pin "+") (pinfunction "+_+") (pintype "passive"))
      (node (ref "R8") (pin "2") (pinfunction "2_2") (pintype "passive"))
      (node (ref "V1") (pin "8") (pinfunction "TK_8") (pintype "passive"))
    )
    (net (code "67") (name "Net-(VOLUMEA-2)") (class "Default")
      (node (ref "VOLUME") (pin "O1") (pinfunction "2_O1") (pintype "passive"))
      (node (ref "VOL_OUT") (pin "1") (pinfunction "S_1") (pintype "passive"))
    )
    (net (code "68") (name "Net-(VOLUMEA-3)") (class "Default")
      (node (ref "VOLUME") (pin "I1") (pinfunction "3_I1") (pintype "passive"))
      (node (ref "VOL_IN") (pin "1") (pinfunction "S_1") (pintype "passive"))
    )
    (net (code "69") (name "Net-(VOLUMEB-2)") (class "Default")
      (node (ref "VOLUME") (pin "O2") (pinfunction "2_O2") (pintype "passive"))
      (node (ref "VOL_OUT") (pin "3") (pinfunction "S_3") (pintype "passive"))
    )
    (net (code "70") (name "Net-(VOLUMEB-3)") (class "Default")
      (node (ref "VOLUME") (pin "I2") (pinfunction "3_I2") (pintype "passive"))
      (node (ref "VOL_IN") (pin "3") (pinfunction "S_3") (pintype "passive"))
    )
    (net (code "71") (name "Net-(VOL_INB-S)") (class "Default")
      (node (ref "VOL_IN") (pin "2") (pinfunction "S_2") (pintype "passive"))
      (node (ref "VOL_OUT") (pin "2") (pinfunction "S_2") (pintype "passive"))
    )
    (net (code "72") (name "OUTPUT_L") (class "Default")
      (node (ref "C3") (pin "-") (pinfunction "-_-") (pintype "passive"))
      (node (ref "OUTPUT") (pin "1") (pinfunction "S_1") (pintype "passive"))
      (node (ref "R4") (pin "2") (pinfunction "2_2") (pintype "passive"))
    )
    (net (code "73") (name "OUTPUT_R") (class "Default")
      (node (ref "C4") (pin "-") (pinfunction "-_-") (pintype "passive"))
      (node (ref "OUTPUT") (pin "3") (pinfunction "S_3") (pintype "passive"))
      (node (ref "R10") (pin "2") (pinfunction "2_2") (pintype "passive"))
    )
    (net (code "74") (name "VCC") (class "Default")
      (node (ref "C10") (pin "1") (pinfunction "1_1") (pintype "passive"))
      (node (ref "C11") (pin "1") (pinfunction "1_1") (pintype "passive"))
      (node (ref "C16") (pin "1") (pinfunction "1_1") (pintype "passive"))
      (node (ref "C7") (pin "+") (pinfunction "+_+") (pintype "passive"))
      (node (ref "C8") (pin "+") (pinfunction "+_+") (pintype "passive"))
      (node (ref "D1") (pin "C") (pinfunction "C_C") (pintype "passive"))
      (node (ref "D4") (pin "C") (pinfunction "C_C") (pintype "passive"))
      (node (ref "D5") (pin "C") (pinfunction "C_C") (pintype "passive"))
      (node (ref "DLY_PWR1") (pin "1") (pinfunction "S_1") (pintype "passive"))
      (node (ref "FILAMENT_PWR") (pin "3") (pinfunction "S_3") (pintype "passive"))
      (node (ref "IC3") (pin "3") (pinfunction "IN_3") (pintype "input"))
      (node (ref "IC4") (pin "2") (pinfunction "IN_2") (pintype "input"))
      (node (ref "IC5") (pin "1") (pinfunction "VI_1") (pintype "input"))
      (node (ref "PSU_AUX") (pin "2") (pinfunction "S_2") (pintype "passive"))
      (node (ref "PSU_AUX1") (pin "2") (pinfunction "S_2") (pintype "passive"))
      (node (ref "PSU_AUX2") (pin "2") (pinfunction "S_2") (pintype "passive"))
      (node (ref "V1") (pin "5") (pinfunction "H3_5") (pintype "passive"))
    )
    (net (code "75") (name "unconnected-(J2-Pad2)") (class "Default")
      (node (ref "J2") (pin "2") (pinfunction "2_2") (pintype "passive"))
    )
    (net (code "76") (name "unconnected-(JP1-EARTH-NORM-PadSLEEVE-NORM)") (class "Default")
      (node (ref "JP1") (pin "SLEEVE-NORM") (pinfunction "EARTH-NORM_SLEEVE-NORM") (pintype "bidirectional"))
    )
    (net (code "77") (name "unconnected-(JP1-PadRING-NORM)") (class "Default")
      (node (ref "JP1") (pin "RING-NORM") (pinfunction "RING-NORM_RING-NORM") (pintype "bidirectional"))
    )
    (net (code "78") (name "unconnected-(JP1-PadTIP-NORM)") (class "Default")
      (node (ref "JP1") (pin "TIP-NORM") (pinfunction "TIP-NORM_TIP-NORM") (pintype "bidirectional"))
    )
    (net (code "79") (name "unconnected-(K1B-O-PadO1)") (class "Default")
      (node (ref "K1") (pin "O1") (pinfunction "O_O1") (pintype "passive"))
    )
    (net (code "80") (name "unconnected-(K1C-O-PadO2)") (class "Default")
      (node (ref "K1") (pin "O2") (pinfunction "O_O2") (pintype "passive"))
    )
    (net (code "81") (name "unconnected-(VOLUMEA-1-PadG1)") (class "Default")
      (node (ref "VOLUME") (pin "G1") (pinfunction "1_G1") (pintype "passive"))
    )
    (net (code "82") (name "unconnected-(VOLUMEB-1-PadG2)") (class "Default")
      (node (ref "VOLUME") (pin "G2") (pinfunction "1_G2") (pintype "passive"))
    )
  )
)
